# SCH_Project_2026-06-06.net
KiCad netlist of a schematic drawn in EasyEDA
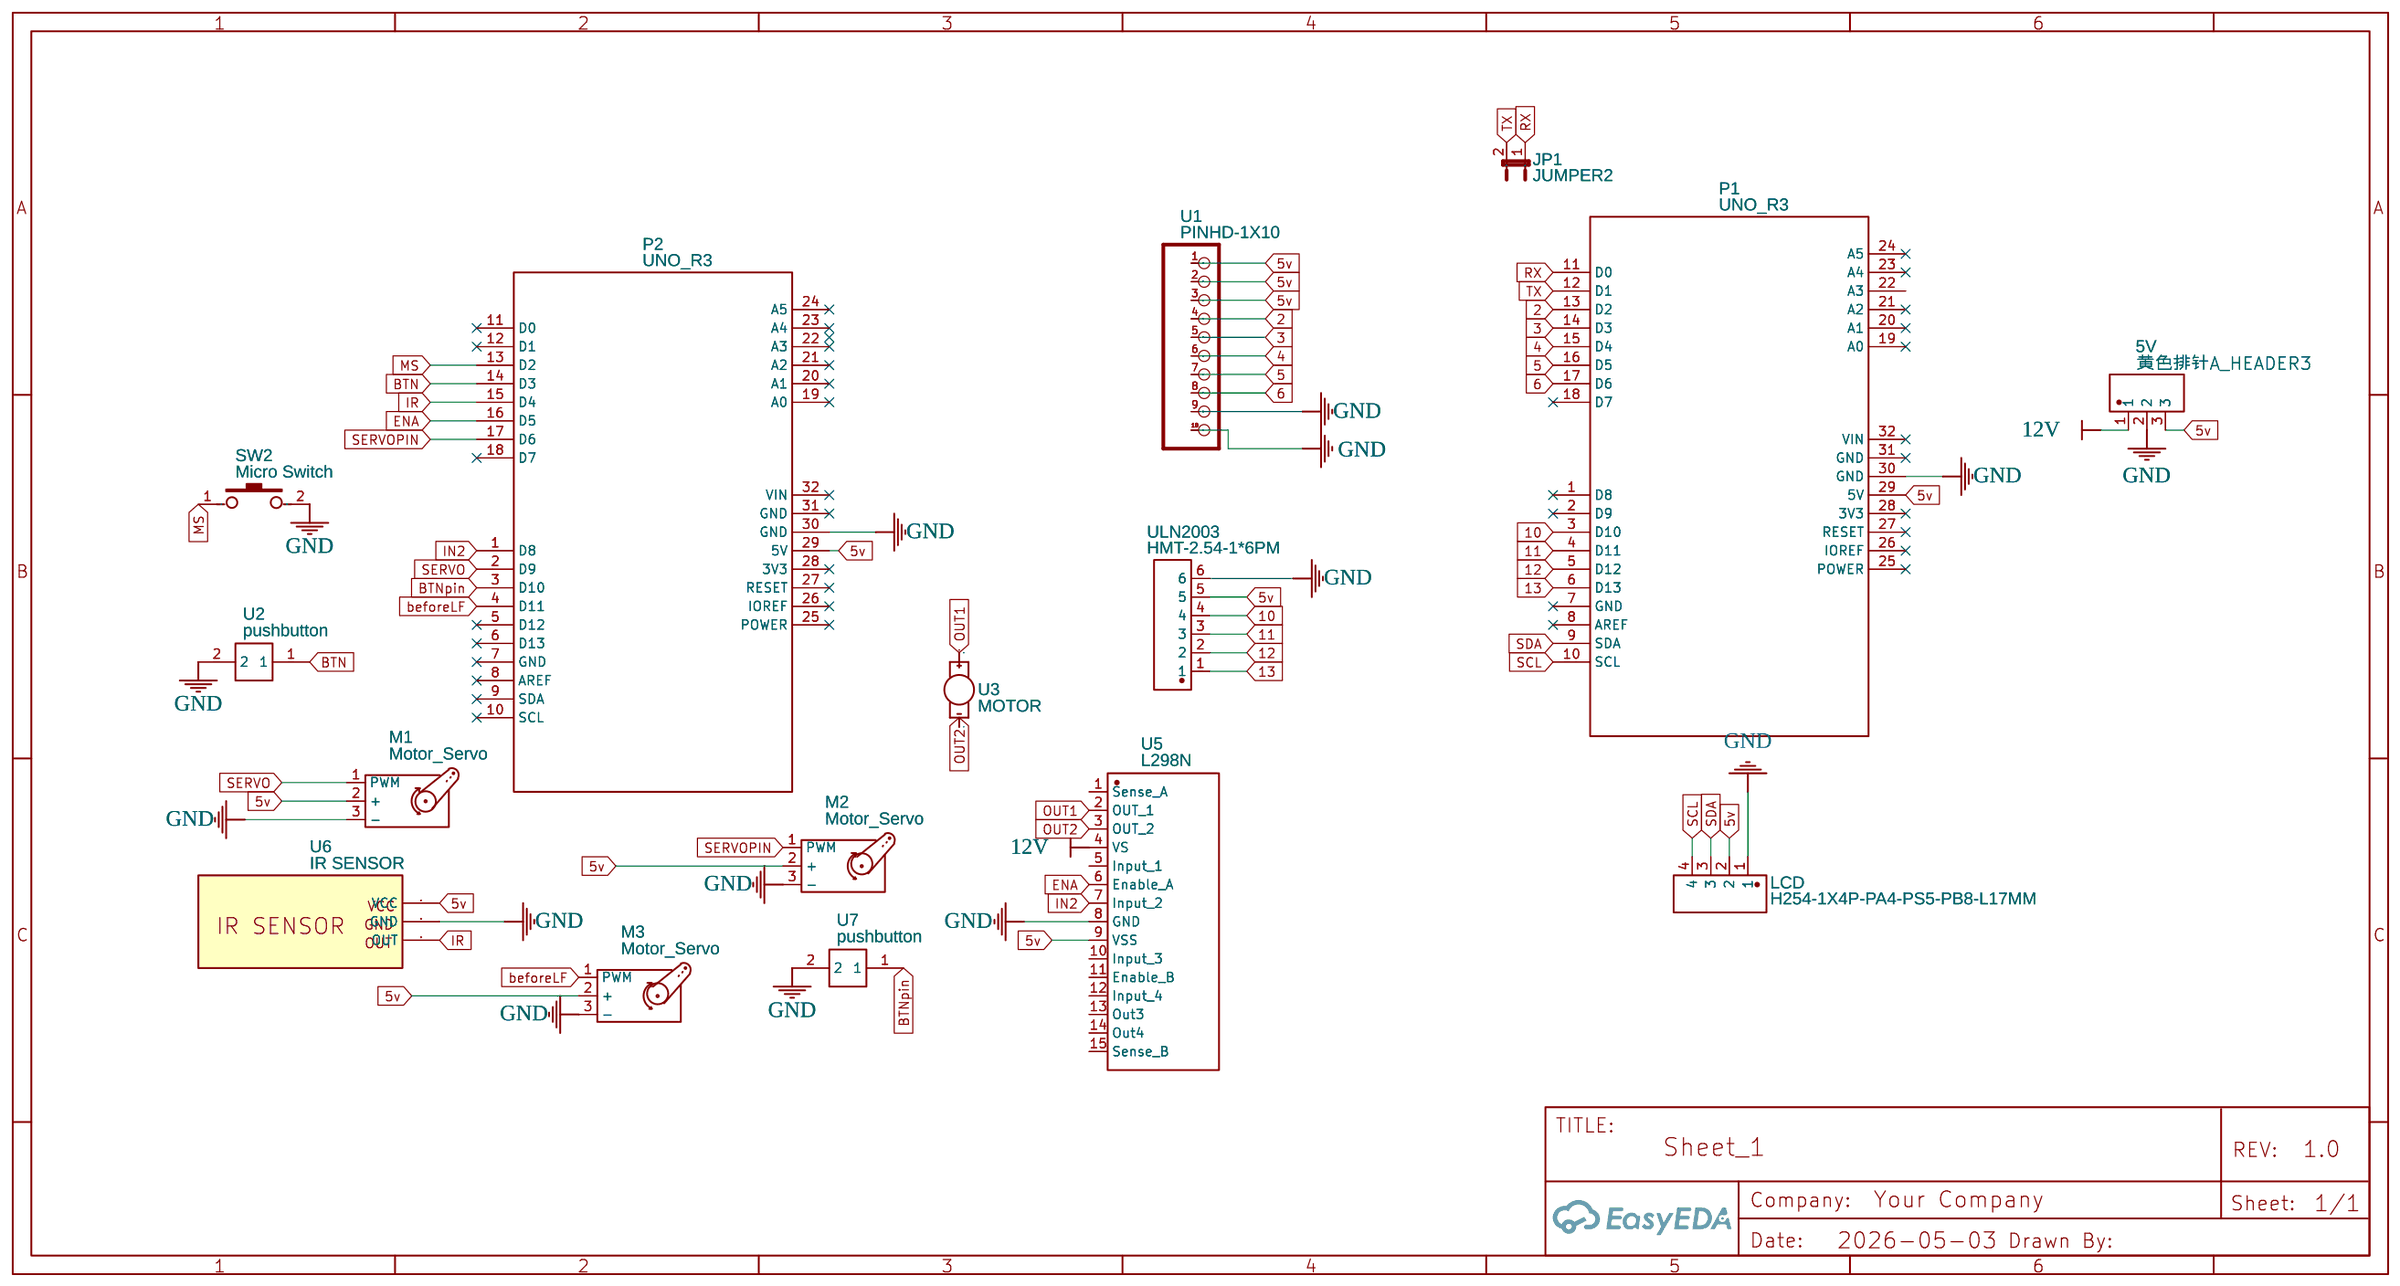
[diagram p0: schematic sheet]

(export (version "E")
  (design (tool "Eeschema 10.0.6"))
  (components
    (comp (ref "5V") (value "黄色排针A_HEADER3") (libsource (lib "") (part "黄色排针A_HEADER3")))
    (comp (ref "JP1") (value "JUMPER2") (libsource (lib "") (part "JUMPER2")))
    (comp (ref "LCD")
      (value "H254-1X4P-PA4-PS5-PB8-L17MM")
      (libsource (lib "") (part "H254-1X4P-PA4-PS5-PB8-L17MM"))
    )
    (comp (ref "M1") (value "Motor_Servo") (libsource (lib "") (part "Motor_Servo_1")))
    (comp (ref "M2") (value "Motor_Servo") (libsource (lib "") (part "Motor_Servo")))
    (comp (ref "M3") (value "Motor_Servo") (libsource (lib "") (part "Motor_Servo")))
    (comp (ref "P1") (value "UNO_R3") (libsource (lib "") (part "UNO_R3")))
    (comp (ref "P2") (value "UNO_R3") (libsource (lib "") (part "UNO_R3")))
    (comp (ref "SW2") (value "Micro Switch") (libsource (lib "") (part "Micro Switch")))
    (comp (ref "U1") (value "PINHD-1X10") (libsource (lib "") (part "PINHD-1X10")))
    (comp (ref "U2") (value "pushbutton") (libsource (lib "") (part "pushbutton")))
    (comp (ref "U3") (value "MOTOR") (libsource (lib "") (part "MOTOR")))
    (comp (ref "U5")
      (value "L298N")
      (fields (field (name "Manufacturer") "HGSEMI(华冠)"))
      (libsource (lib "") (part "L298N"))
    )
    (comp (ref "U6") (value "IR SENSOR") (libsource (lib "") (part "MH-Sensor-Series Line Sensor")))
    (comp (ref "U7") (value "pushbutton") (libsource (lib "") (part "pushbutton")))
    (comp (ref "ULN2003")
      (value "HMT-2.54-1*6PM")
      (fields (field (name "Manufacturer") "HMTCONN(华明通)"))
      (libsource (lib "") (part "HMT-2.54-1*6PM"))
    )
  )
  (nets
    (net (code "1") (name "2") (class "Default")
      (node (ref "P1") (pin "13") (pinfunction "D2_13") (pintype "unspecified"))
      (node (ref "U1") (pin "4") (pinfunction "4_4") (pintype "unspecified"))
    )
    (net (code "2") (name "3") (class "Default")
      (node (ref "P1") (pin "14") (pinfunction "D3_14") (pintype "unspecified"))
      (node (ref "U1") (pin "5") (pinfunction "5_5") (pintype "unspecified"))
    )
    (net (code "3") (name "4") (class "Default")
      (node (ref "P1") (pin "15") (pinfunction "D4_15") (pintype "unspecified"))
      (node (ref "U1") (pin "6") (pinfunction "6_6") (pintype "unspecified"))
    )
    (net (code "4") (name "5") (class "Default")
      (node (ref "P1") (pin "16") (pinfunction "D5_16") (pintype "unspecified"))
      (node (ref "U1") (pin "7") (pinfunction "7_7") (pintype "unspecified"))
    )
    (net (code "5") (name "5v") (class "Default")
      (node (ref "5V") (pin "3") (pinfunction "3_3") (pintype "unspecified"))
      (node (ref "LCD") (pin "2") (pinfunction "2_2") (pintype "unspecified"))
      (node (ref "M1") (pin "2") (pinfunction "+_2") (pintype "unspecified"))
      (node (ref "M2") (pin "2") (pinfunction "+_2") (pintype "unspecified"))
      (node (ref "M3") (pin "2") (pinfunction "+_2") (pintype "unspecified"))
      (node (ref "P1") (pin "29") (pinfunction "5V_29") (pintype "unspecified"))
      (node (ref "P2") (pin "29") (pinfunction "5V_29") (pintype "unspecified"))
      (node (ref "U1") (pin "1") (pinfunction "1_1") (pintype "unspecified"))
      (node (ref "U1") (pin "2") (pinfunction "2_2") (pintype "unspecified"))
      (node (ref "U1") (pin "3") (pinfunction "3_3") (pintype "unspecified"))
      (node (ref "U5") (pin "9") (pinfunction "VSS_9") (pintype "unspecified"))
      (node (ref "U6") (pin "4") (pinfunction "VCC_4") (pintype "unspecified"))
      (node (ref "ULN2003") (pin "5") (pinfunction "5_5") (pintype "unspecified"))
    )
    (net (code "6") (name "6") (class "Default")
      (node (ref "P1") (pin "17") (pinfunction "D6_17") (pintype "unspecified"))
      (node (ref "U1") (pin "8") (pinfunction "8_8") (pintype "unspecified"))
    )
    (net (code "7") (name "10") (class "Default")
      (node (ref "P1") (pin "3") (pinfunction "D10_3") (pintype "unspecified"))
      (node (ref "ULN2003") (pin "4") (pinfunction "4_4") (pintype "unspecified"))
    )
    (net (code "8") (name "11") (class "Default")
      (node (ref "P1") (pin "4") (pinfunction "D11_4") (pintype "unspecified"))
      (node (ref "ULN2003") (pin "3") (pinfunction "3_3") (pintype "unspecified"))
    )
    (net (code "9") (name "12") (class "Default")
      (node (ref "P1") (pin "5") (pinfunction "D12_5") (pintype "unspecified"))
      (node (ref "ULN2003") (pin "2") (pinfunction "2_2") (pintype "unspecified"))
    )
    (net (code "10") (name "12V") (class "Default")
      (node (ref "5V") (pin "1") (pinfunction "1_1") (pintype "unspecified"))
      (node (ref "U5") (pin "4") (pinfunction "VS_4") (pintype "unspecified"))
    )
    (net (code "11") (name "13") (class "Default")
      (node (ref "P1") (pin "6") (pinfunction "D13_6") (pintype "unspecified"))
      (node (ref "ULN2003") (pin "1") (pinfunction "1_1") (pintype "unspecified"))
    )
    (net (code "12") (name "BTN") (class "Default")
      (node (ref "P2") (pin "14") (pinfunction "D3_14") (pintype "unspecified"))
      (node (ref "U2") (pin "1") (pinfunction "1_1") (pintype "unspecified"))
    )
    (net (code "13") (name "BTNpin") (class "Default")
      (node (ref "P2") (pin "3") (pinfunction "D10_3") (pintype "unspecified"))
      (node (ref "U7") (pin "1") (pinfunction "1_1") (pintype "unspecified"))
    )
    (net (code "14") (name "ENA") (class "Default")
      (node (ref "P2") (pin "16") (pinfunction "D5_16") (pintype "unspecified"))
      (node (ref "U5") (pin "6") (pinfunction "Enable_A_6") (pintype "unspecified"))
    )
    (net (code "15") (name "GND") (class "Default")
      (node (ref "5V") (pin "2") (pinfunction "2_2") (pintype "unspecified"))
      (node (ref "LCD") (pin "1") (pinfunction "1_1") (pintype "unspecified"))
      (node (ref "M1") (pin "3") (pinfunction "-_3") (pintype "unspecified"))
      (node (ref "M2") (pin "3") (pinfunction "-_3") (pintype "unspecified"))
      (node (ref "M3") (pin "3") (pinfunction "-_3") (pintype "unspecified"))
      (node (ref "P1") (pin "30") (pinfunction "GND_30") (pintype "unspecified"))
      (node (ref "P2") (pin "30") (pinfunction "GND_30") (pintype "unspecified"))
      (node (ref "SW2") (pin "2") (pinfunction "2_2") (pintype "input"))
      (node (ref "U1") (pin "10") (pinfunction "10_10") (pintype "unspecified"))
      (node (ref "U1") (pin "9") (pinfunction "9_9") (pintype "unspecified"))
      (node (ref "U2") (pin "2") (pinfunction "2_2") (pintype "unspecified"))
      (node (ref "U5") (pin "8") (pinfunction "GND_8") (pintype "unspecified"))
      (node (ref "U6") (pin "3") (pinfunction "GND_3") (pintype "unspecified"))
      (node (ref "U7") (pin "2") (pinfunction "2_2") (pintype "unspecified"))
      (node (ref "ULN2003") (pin "6") (pinfunction "6_6") (pintype "unspecified"))
    )
    (net (code "16") (name "IN2") (class "Default")
      (node (ref "P2") (pin "1") (pinfunction "D8_1") (pintype "unspecified"))
      (node (ref "U5") (pin "7") (pinfunction "Input_2_7") (pintype "unspecified"))
    )
    (net (code "17") (name "IR") (class "Default")
      (node (ref "P2") (pin "15") (pinfunction "D4_15") (pintype "unspecified"))
      (node (ref "U6") (pin "2") (pinfunction "OUT_2") (pintype "unspecified"))
    )
    (net (code "18") (name "MS") (class "Default")
      (node (ref "P2") (pin "13") (pinfunction "D2_13") (pintype "unspecified"))
      (node (ref "SW2") (pin "1") (pinfunction "1_1") (pintype "input"))
    )
    (net (code "19") (name "OUT1") (class "Default")
      (node (ref "U3") (pin "+") (pinfunction "+_+") (pintype "unspecified"))
      (node (ref "U5") (pin "2") (pinfunction "OUT_1_2") (pintype "unspecified"))
    )
    (net (code "20") (name "OUT2") (class "Default")
      (node (ref "U5") (pin "3") (pinfunction "OUT_2_3") (pintype "unspecified"))
    )
    (net (code "21") (name "RX") (class "Default")
      (node (ref "JP1") (pin "1") (pinfunction "1_1") (pintype "unspecified"))
      (node (ref "P1") (pin "11") (pinfunction "D0_11") (pintype "unspecified"))
    )
    (net (code "22") (name "SCL") (class "Default")
      (node (ref "LCD") (pin "4") (pinfunction "4_4") (pintype "unspecified"))
      (node (ref "P1") (pin "10") (pinfunction "SCL_10") (pintype "unspecified"))
    )
    (net (code "23") (name "SDA") (class "Default")
      (node (ref "LCD") (pin "3") (pinfunction "3_3") (pintype "unspecified"))
      (node (ref "P1") (pin "9") (pinfunction "SDA_9") (pintype "unspecified"))
    )
    (net (code "24") (name "SERVO") (class "Default")
      (node (ref "M1") (pin "1") (pinfunction "PWM_1") (pintype "unspecified"))
      (node (ref "P2") (pin "2") (pinfunction "D9_2") (pintype "unspecified"))
    )
    (net (code "25") (name "SERVOPIN") (class "Default")
      (node (ref "M2") (pin "1") (pinfunction "PWM_1") (pintype "unspecified"))
      (node (ref "P2") (pin "17") (pinfunction "D6_17") (pintype "unspecified"))
    )
    (net (code "26") (name "TX") (class "Default")
      (node (ref "JP1") (pin "2") (pinfunction "2_2") (pintype "unspecified"))
      (node (ref "P1") (pin "12") (pinfunction "D1_12") (pintype "unspecified"))
    )
    (net (code "27") (name "beforeLF") (class "Default")
      (node (ref "M3") (pin "1") (pinfunction "PWM_1") (pintype "unspecified"))
      (node (ref "P2") (pin "4") (pinfunction "D11_4") (pintype "unspecified"))
    )
    (net (code "28") (name "unconnected-(P1-3V3-Pad28)") (class "Default")
      (node (ref "P1") (pin "28") (pinfunction "3V3_28") (pintype "unspecified+no_connect"))
    )
    (net (code "29") (name "unconnected-(P1-A0-Pad19)") (class "Default")
      (node (ref "P1") (pin "19") (pinfunction "A0_19") (pintype "unspecified+no_connect"))
    )
    (net (code "30") (name "unconnected-(P1-A1-Pad20)") (class "Default")
      (node (ref "P1") (pin "20") (pinfunction "A1_20") (pintype "unspecified+no_connect"))
    )
    (net (code "31") (name "unconnected-(P1-A2-Pad21)") (class "Default")
      (node (ref "P1") (pin "21") (pinfunction "A2_21") (pintype "unspecified+no_connect"))
    )
    (net (code "32") (name "unconnected-(P1-A3-Pad22)") (class "Default")
      (node (ref "P1") (pin "22") (pinfunction "A3_22") (pintype "unspecified"))
    )
    (net (code "33") (name "unconnected-(P1-A4-Pad23)") (class "Default")
      (node (ref "P1") (pin "23") (pinfunction "A4_23") (pintype "unspecified+no_connect"))
    )
    (net (code "34") (name "unconnected-(P1-A5-Pad24)") (class "Default")
      (node (ref "P1") (pin "24") (pinfunction "A5_24") (pintype "unspecified+no_connect"))
    )
    (net (code "35") (name "unconnected-(P1-AREF-Pad8)") (class "Default")
      (node (ref "P1") (pin "8") (pinfunction "AREF_8") (pintype "unspecified+no_connect"))
    )
    (net (code "36") (name "unconnected-(P1-D7-Pad18)") (class "Default")
      (node (ref "P1") (pin "18") (pinfunction "D7_18") (pintype "unspecified+no_connect"))
    )
    (net (code "37") (name "unconnected-(P1-D8-Pad1)") (class "Default")
      (node (ref "P1") (pin "1") (pinfunction "D8_1") (pintype "unspecified+no_connect"))
    )
    (net (code "38") (name "unconnected-(P1-D9-Pad2)") (class "Default")
      (node (ref "P1") (pin "2") (pinfunction "D9_2") (pintype "unspecified+no_connect"))
    )
    (net (code "39") (name "unconnected-(P1-GND-Pad7)") (class "Default")
      (node (ref "P1") (pin "7") (pinfunction "GND_7") (pintype "unspecified+no_connect"))
    )
    (net (code "40") (name "unconnected-(P1-GND-Pad31)") (class "Default")
      (node (ref "P1") (pin "31") (pinfunction "GND_31") (pintype "unspecified+no_connect"))
    )
    (net (code "41") (name "unconnected-(P1-IOREF-Pad26)") (class "Default")
      (node (ref "P1") (pin "26") (pinfunction "IOREF_26") (pintype "unspecified+no_connect"))
    )
    (net (code "42") (name "unconnected-(P1-POWER-Pad25)") (class "Default")
      (node (ref "P1") (pin "25") (pinfunction "POWER_25") (pintype "unspecified+no_connect"))
    )
    (net (code "43") (name "unconnected-(P1-RESET-Pad27)") (class "Default")
      (node (ref "P1") (pin "27") (pinfunction "RESET_27") (pintype "unspecified+no_connect"))
    )
    (net (code "44") (name "unconnected-(P1-VIN-Pad32)") (class "Default")
      (node (ref "P1") (pin "32") (pinfunction "VIN_32") (pintype "unspecified+no_connect"))
    )
    (net (code "45") (name "unconnected-(P2-3V3-Pad28)") (class "Default")
      (node (ref "P2") (pin "28") (pinfunction "3V3_28") (pintype "unspecified+no_connect"))
    )
    (net (code "46") (name "unconnected-(P2-A0-Pad19)") (class "Default")
      (node (ref "P2") (pin "19") (pinfunction "A0_19") (pintype "unspecified+no_connect"))
    )
    (net (code "47") (name "unconnected-(P2-A1-Pad20)") (class "Default")
      (node (ref "P2") (pin "20") (pinfunction "A1_20") (pintype "unspecified+no_connect"))
    )
    (net (code "48") (name "unconnected-(P2-A2-Pad21)") (class "Default")
      (node (ref "P2") (pin "21") (pinfunction "A2_21") (pintype "unspecified+no_connect"))
    )
    (net (code "49") (name "unconnected-(P2-A3-Pad22)") (class "Default")
      (node (ref "P2") (pin "22") (pinfunction "A3_22") (pintype "unspecified+no_connect"))
    )
    (net (code "50") (name "unconnected-(P2-A4-Pad23)") (class "Default")
      (node (ref "P2") (pin "23") (pinfunction "A4_23") (pintype "unspecified+no_connect"))
    )
    (net (code "51") (name "unconnected-(P2-A5-Pad24)") (class "Default")
      (node (ref "P2") (pin "24") (pinfunction "A5_24") (pintype "unspecified+no_connect"))
    )
    (net (code "52") (name "unconnected-(P2-AREF-Pad8)") (class "Default")
      (node (ref "P2") (pin "8") (pinfunction "AREF_8") (pintype "unspecified+no_connect"))
    )
    (net (code "53") (name "unconnected-(P2-D0-Pad11)") (class "Default")
      (node (ref "P2") (pin "11") (pinfunction "D0_11") (pintype "unspecified+no_connect"))
    )
    (net (code "54") (name "unconnected-(P2-D1-Pad12)") (class "Default")
      (node (ref "P2") (pin "12") (pinfunction "D1_12") (pintype "unspecified+no_connect"))
    )
    (net (code "55") (name "unconnected-(P2-D7-Pad18)") (class "Default")
      (node (ref "P2") (pin "18") (pinfunction "D7_18") (pintype "unspecified+no_connect"))
    )
    (net (code "56") (name "unconnected-(P2-D12-Pad5)") (class "Default")
      (node (ref "P2") (pin "5") (pinfunction "D12_5") (pintype "unspecified+no_connect"))
    )
    (net (code "57") (name "unconnected-(P2-D13-Pad6)") (class "Default")
      (node (ref "P2") (pin "6") (pinfunction "D13_6") (pintype "unspecified+no_connect"))
    )
    (net (code "58") (name "unconnected-(P2-GND-Pad7)") (class "Default")
      (node (ref "P2") (pin "7") (pinfunction "GND_7") (pintype "unspecified+no_connect"))
    )
    (net (code "59") (name "unconnected-(P2-GND-Pad31)") (class "Default")
      (node (ref "P2") (pin "31") (pinfunction "GND_31") (pintype "unspecified+no_connect"))
    )
    (net (code "60") (name "unconnected-(P2-IOREF-Pad26)") (class "Default")
      (node (ref "P2") (pin "26") (pinfunction "IOREF_26") (pintype "unspecified+no_connect"))
    )
    (net (code "61") (name "unconnected-(P2-POWER-Pad25)") (class "Default")
      (node (ref "P2") (pin "25") (pinfunction "POWER_25") (pintype "unspecified+no_connect"))
    )
    (net (code "62") (name "unconnected-(P2-RESET-Pad27)") (class "Default")
      (node (ref "P2") (pin "27") (pinfunction "RESET_27") (pintype "unspecified+no_connect"))
    )
    (net (code "63") (name "unconnected-(P2-SCL-Pad10)") (class "Default")
      (node (ref "P2") (pin "10") (pinfunction "SCL_10") (pintype "unspecified+no_connect"))
    )
    (net (code "64") (name "unconnected-(P2-SDA-Pad9)") (class "Default")
      (node (ref "P2") (pin "9") (pinfunction "SDA_9") (pintype "unspecified+no_connect"))
    )
    (net (code "65") (name "unconnected-(P2-VIN-Pad32)") (class "Default")
      (node (ref "P2") (pin "32") (pinfunction "VIN_32") (pintype "unspecified+no_connect"))
    )
    (net (code "66") (name "unconnected-(U3-Pad-)") (class "Default")
      (node (ref "U3") (pin "-") (pinfunction "-_-") (pintype "unspecified"))
    )
    (net (code "67") (name "unconnected-(U5-Enable_B-Pad11)") (class "Default")
      (node (ref "U5") (pin "11") (pinfunction "Enable_B_11") (pintype "unspecified"))
    )
    (net (code "68") (name "unconnected-(U5-Input_1-Pad5)") (class "Default")
      (node (ref "U5") (pin "5") (pinfunction "Input_1_5") (pintype "unspecified"))
    )
    (net (code "69") (name "unconnected-(U5-Input_3-Pad10)") (class "Default")
      (node (ref "U5") (pin "10") (pinfunction "Input_3_10") (pintype "unspecified"))
    )
    (net (code "70") (name "unconnected-(U5-Input_4-Pad12)") (class "Default")
      (node (ref "U5") (pin "12") (pinfunction "Input_4_12") (pintype "unspecified"))
    )
    (net (code "71") (name "unconnected-(U5-Out3-Pad13)") (class "Default")
      (node (ref "U5") (pin "13") (pinfunction "Out3_13") (pintype "unspecified"))
    )
    (net (code "72") (name "unconnected-(U5-Out4-Pad14)") (class "Default")
      (node (ref "U5") (pin "14") (pinfunction "Out4_14") (pintype "unspecified"))
    )
    (net (code "73") (name "unconnected-(U5-Sense_A-Pad1)") (class "Default")
      (node (ref "U5") (pin "1") (pinfunction "Sense_A_1") (pintype "unspecified"))
    )
    (net (code "74") (name "unconnected-(U5-Sense_B-Pad15)") (class "Default")
      (node (ref "U5") (pin "15") (pinfunction "Sense_B_15") (pintype "unspecified"))
    )
  )
)
